# PSU.net
KiCad netlist of a schematic drawn in Altium Designer
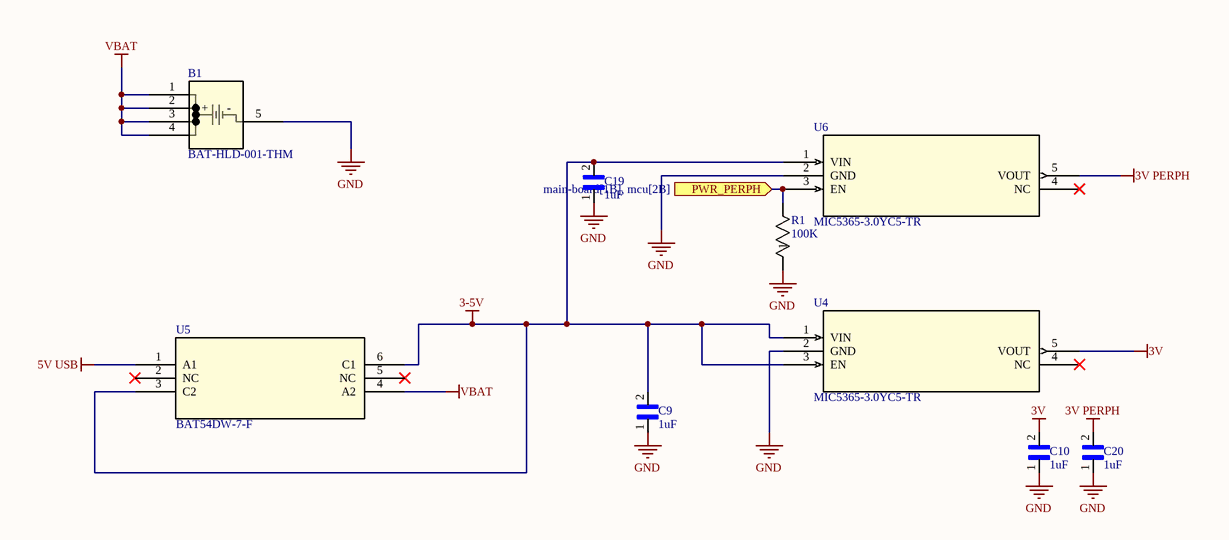
[diagram p0: PSU.SchDoc]

(export (version "E")
  (design (tool "Eeschema 10.0.6"))
  (components
    (comp (ref "B1")
      (value "BAT-HLD-001-THM")
      (footprint "BAT-HLD-001-THM_TEC")
      (libsource (lib "BAT-HLD-001-THM") (part "BAT-HLD-001-THM"))
    )
    (comp (ref "C9")
      (value "1uF")
      (footprint "CAPC1608X90N")
      (fields (field (name "MP") "CL10B105KP8NNNC"))
      (libsource (lib "CL10B105KP8NNNC") (part "CL10B105KP8NNNC"))
    )
    (comp (ref "C10")
      (value "1uF")
      (footprint "CAPC1608X90N")
      (fields (field (name "MP") "CL10B105KP8NNNC"))
      (libsource (lib "CL10B105KP8NNNC") (part "CL10B105KP8NNNC"))
    )
    (comp (ref "C19")
      (value "1uF")
      (footprint "CAPC1608X90N")
      (fields (field (name "MP") "CL10B105KP8NNNC"))
      (libsource (lib "CL10B105KP8NNNC") (part "CL10B105KP8NNNC"))
    )
    (comp (ref "C20")
      (value "1uF")
      (footprint "CAPC1608X90N")
      (description "CL10B105KP8NNNC")
      (libsource (lib "CL10B105KP8NNNC") (part "CL10B105KP8NNNC"))
    )
    (comp (ref "R1")
      (value "100K")
      (footprint "RC0603N_YAG")
      (description "RC0603FR-07100KL")
      (libsource (lib "RC0603FR-07100KL") (part "RC0603FR-07100KL"))
    )
    (comp (ref "U4")
      (value "MIC5365-3.0YC5-TR")
      (footprint "SC-70_C5_MCH")
      (libsource (lib "MIC5365-3P0YC5-TR") (part "MIC5365-3.0YC5-TR"))
    )
    (comp (ref "U5")
      (value "BAT54DW-7-F")
      (footprint "SOT-363_DIO")
      (libsource (lib "BAT54DW-7-F") (part "BAT54DW-7-F"))
    )
    (comp (ref "U6")
      (value "MIC5365-3.0YC5-TR")
      (footprint "SC-70_C5_MCH")
      (libsource (lib "MIC5365-3P0YC5-TR") (part "MIC5365-3.0YC5-TR"))
    )
  )
  (nets
    (net (code "1") (name "/PWR_PERPH") (class "Default")
      (node (ref "R1") (pin "2") (pinfunction "2_2") (pintype "passive"))
      (node (ref "U6") (pin "3") (pinfunction "EN_3") (pintype "input"))
    )
    (net (code "2") (name "3-5V") (class "Default")
      (node (ref "C19") (pin "2") (pinfunction "2_2") (pintype "passive"))
      (node (ref "C9") (pin "2") (pinfunction "2_2") (pintype "passive"))
      (node (ref "U4") (pin "1") (pinfunction "VIN_1") (pintype "input"))
      (node (ref "U4") (pin "3") (pinfunction "EN_3") (pintype "input"))
      (node (ref "U5") (pin "3") (pinfunction "C2_3") (pintype "passive"))
      (node (ref "U5") (pin "6") (pinfunction "C1_6") (pintype "passive"))
      (node (ref "U6") (pin "1") (pinfunction "VIN_1") (pintype "input"))
    )
    (net (code "3") (name "3V") (class "Default")
      (node (ref "C10") (pin "2") (pinfunction "2_2") (pintype "passive"))
      (node (ref "U4") (pin "5") (pinfunction "VOUT_5") (pintype "output"))
    )
    (net (code "4") (name "3V PERPH") (class "Default")
      (node (ref "C20") (pin "2") (pinfunction "2_2") (pintype "passive"))
      (node (ref "U6") (pin "5") (pinfunction "VOUT_5") (pintype "output"))
    )
    (net (code "5") (name "5V USB") (class "Default")
      (node (ref "U5") (pin "1") (pinfunction "A1_1") (pintype "passive"))
    )
    (net (code "6") (name "GND") (class "Default")
      (node (ref "B1") (pin "5") (pinfunction "NEGATIVE_5") (pintype "passive"))
      (node (ref "C10") (pin "1") (pinfunction "1_1") (pintype "passive"))
      (node (ref "C19") (pin "1") (pinfunction "1_1") (pintype "passive"))
      (node (ref "C20") (pin "1") (pinfunction "1_1") (pintype "passive"))
      (node (ref "C9") (pin "1") (pinfunction "1_1") (pintype "passive"))
      (node (ref "R1") (pin "1") (pinfunction "1_1") (pintype "passive"))
      (node (ref "U4") (pin "2") (pinfunction "GND_2") (pintype "power_in"))
      (node (ref "U6") (pin "2") (pinfunction "GND_2") (pintype "power_in"))
    )
    (net (code "7") (name "VBAT") (class "Default")
      (node (ref "B1") (pin "1") (pinfunction "POSITIVE_1") (pintype "passive"))
      (node (ref "B1") (pin "2") (pinfunction "POSITIVE_2") (pintype "passive"))
      (node (ref "B1") (pin "3") (pinfunction "POSITIVE_3") (pintype "passive"))
      (node (ref "B1") (pin "4") (pinfunction "POSITIVE_4") (pintype "passive"))
      (node (ref "U5") (pin "4") (pinfunction "A2_4") (pintype "passive"))
    )
    (net (code "8") (name "unconnected-(U4-NC-Pad4)") (class "Default")
      (node (ref "U4") (pin "4") (pinfunction "NC_4") (pintype "passive+no_connect"))
    )
    (net (code "9") (name "unconnected-(U5-NC-Pad2)") (class "Default")
      (node (ref "U5") (pin "2") (pinfunction "NC_2") (pintype "passive+no_connect"))
    )
    (net (code "10") (name "unconnected-(U5-NC-Pad5)") (class "Default")
      (node (ref "U5") (pin "5") (pinfunction "NC_5") (pintype "passive+no_connect"))
    )
    (net (code "11") (name "unconnected-(U6-NC-Pad4)") (class "Default")
      (node (ref "U6") (pin "4") (pinfunction "NC_4") (pintype "passive+no_connect"))
    )
  )
)
